# mattduino_mega.net
KiCad netlist of a schematic drawn in EAGLE
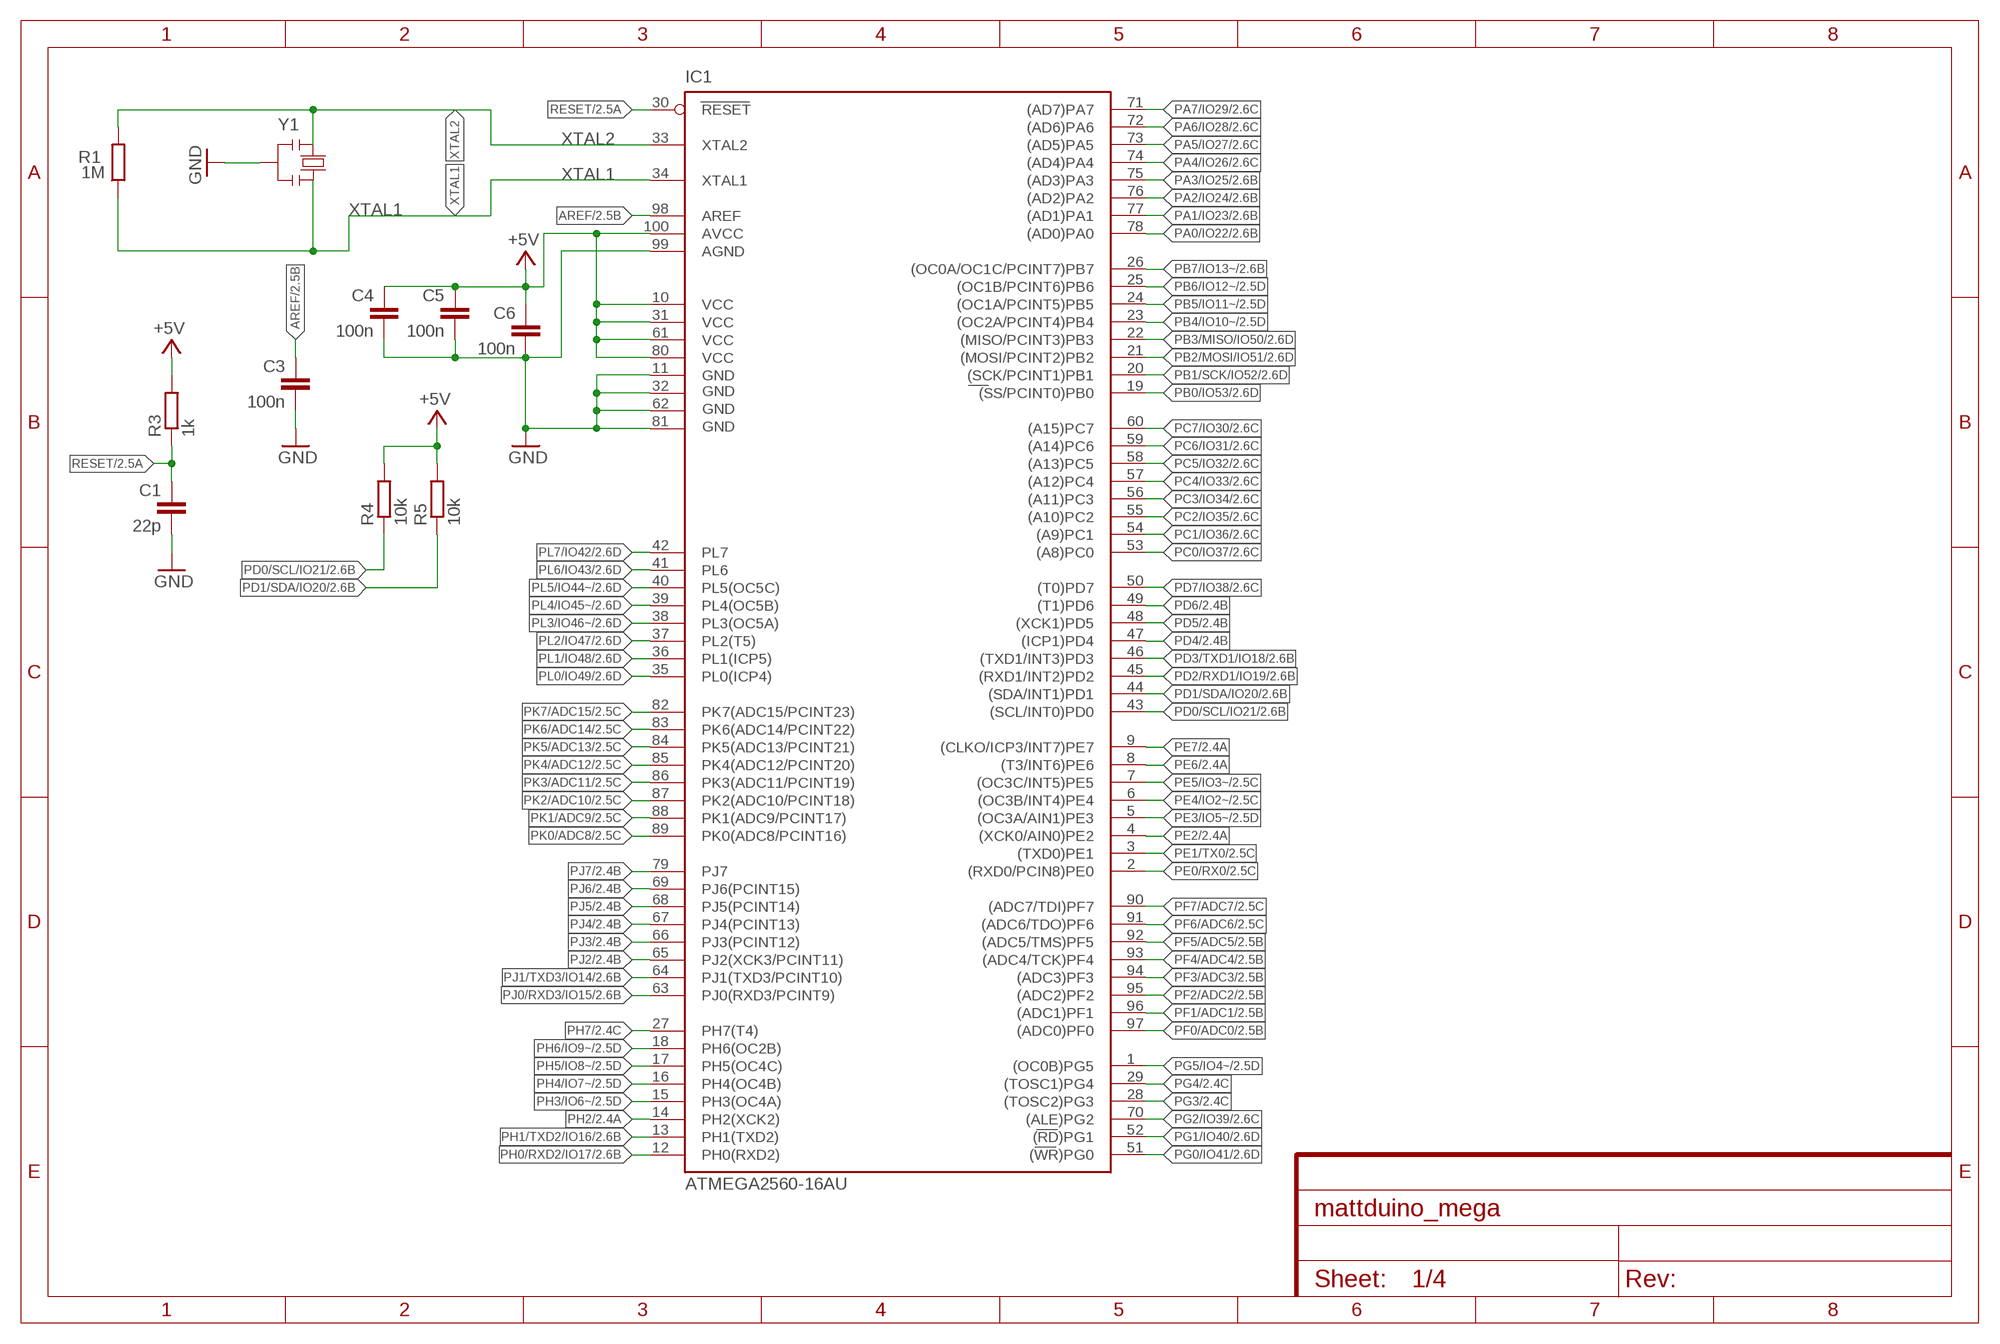
[diagram p0: schematic, sheet 1]
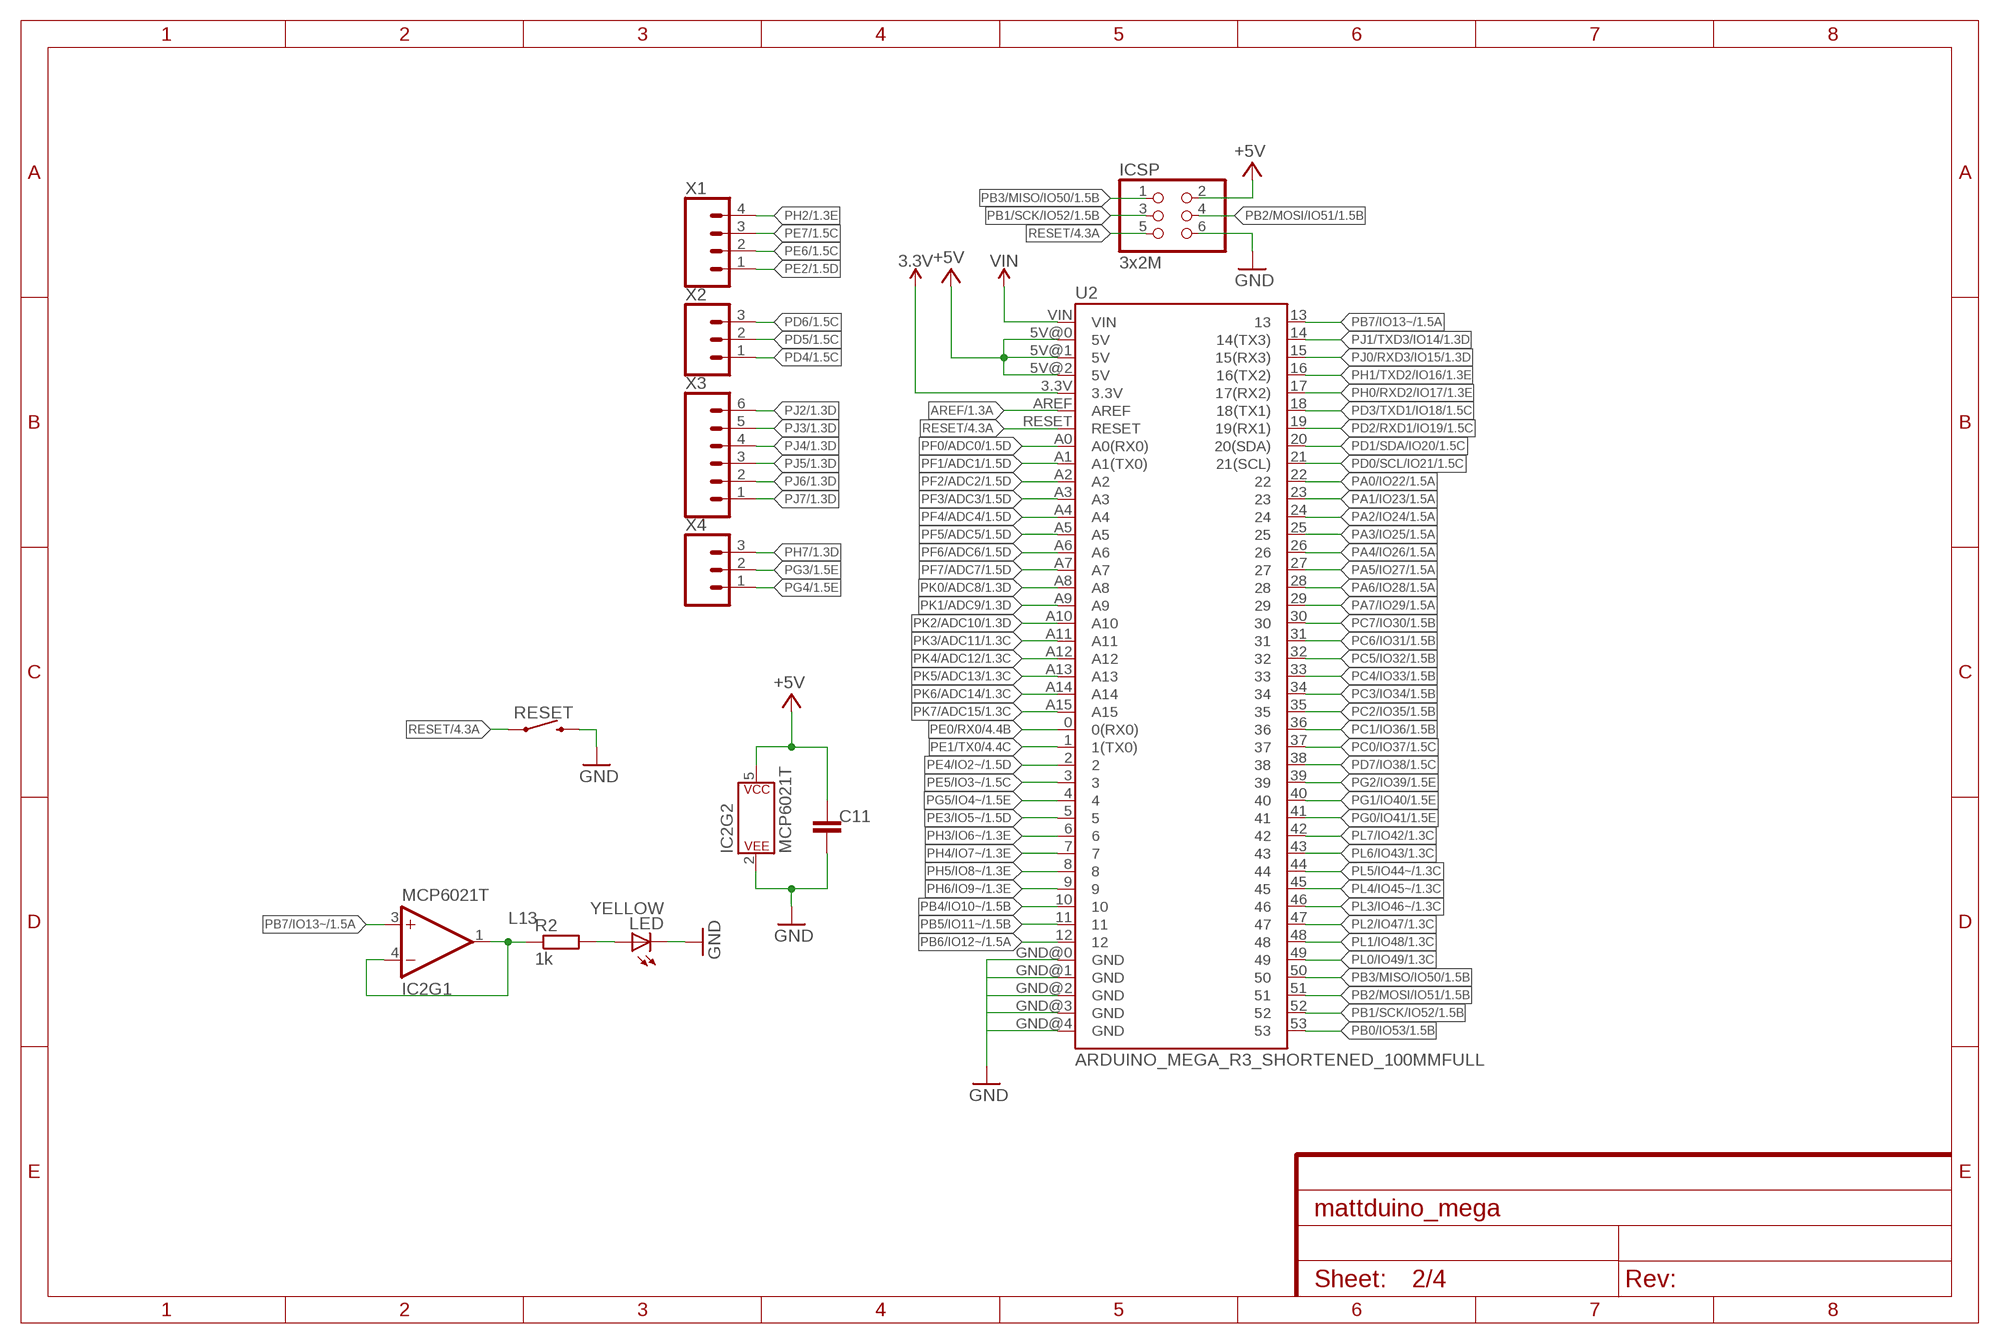
[diagram p1: schematic, sheet 2]
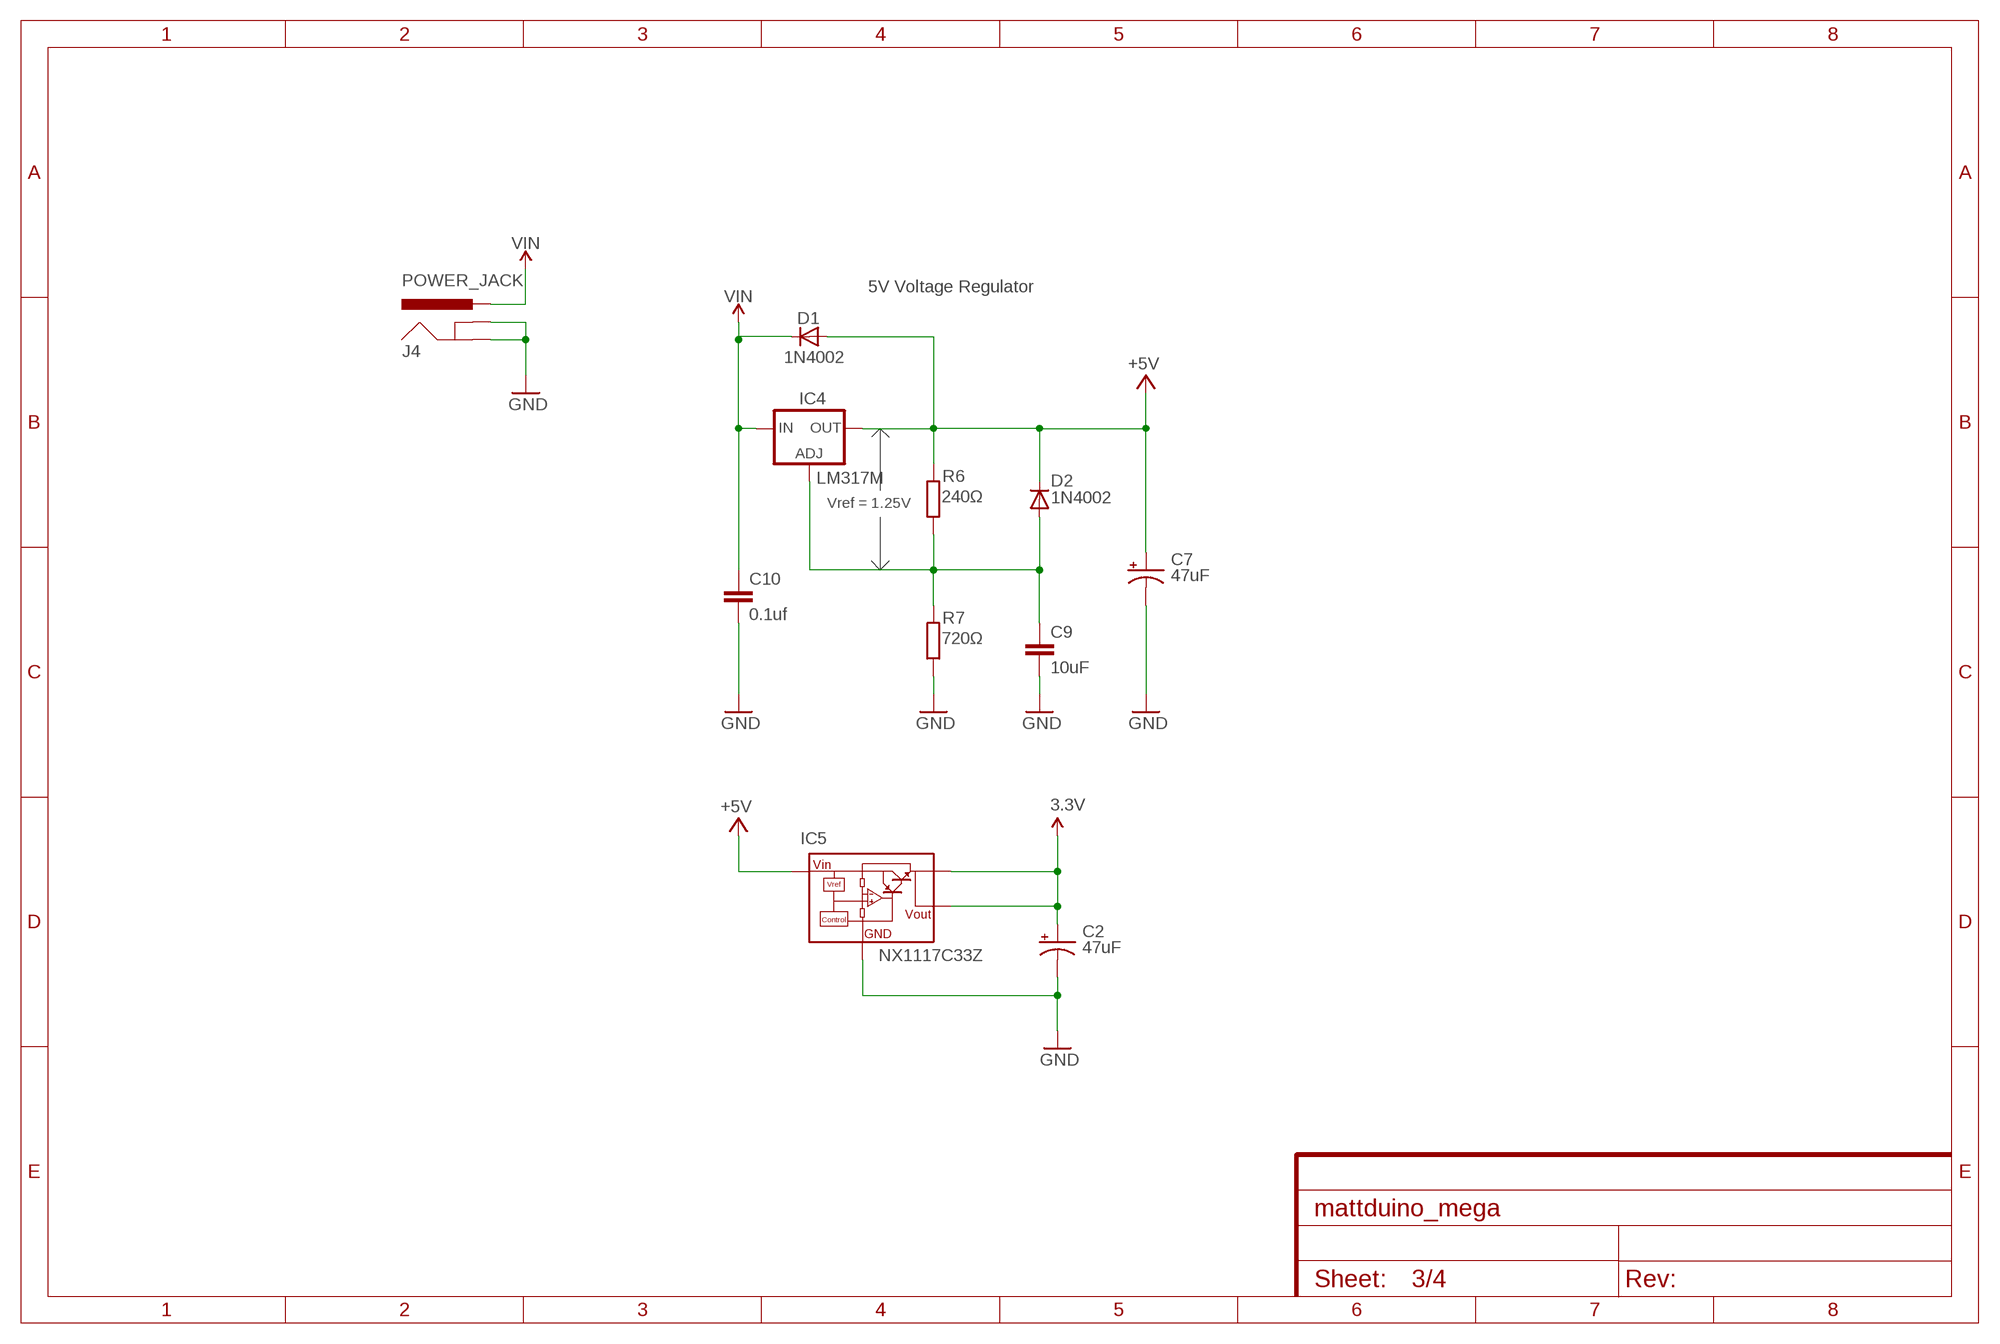
[diagram p2: schematic, sheet 3]
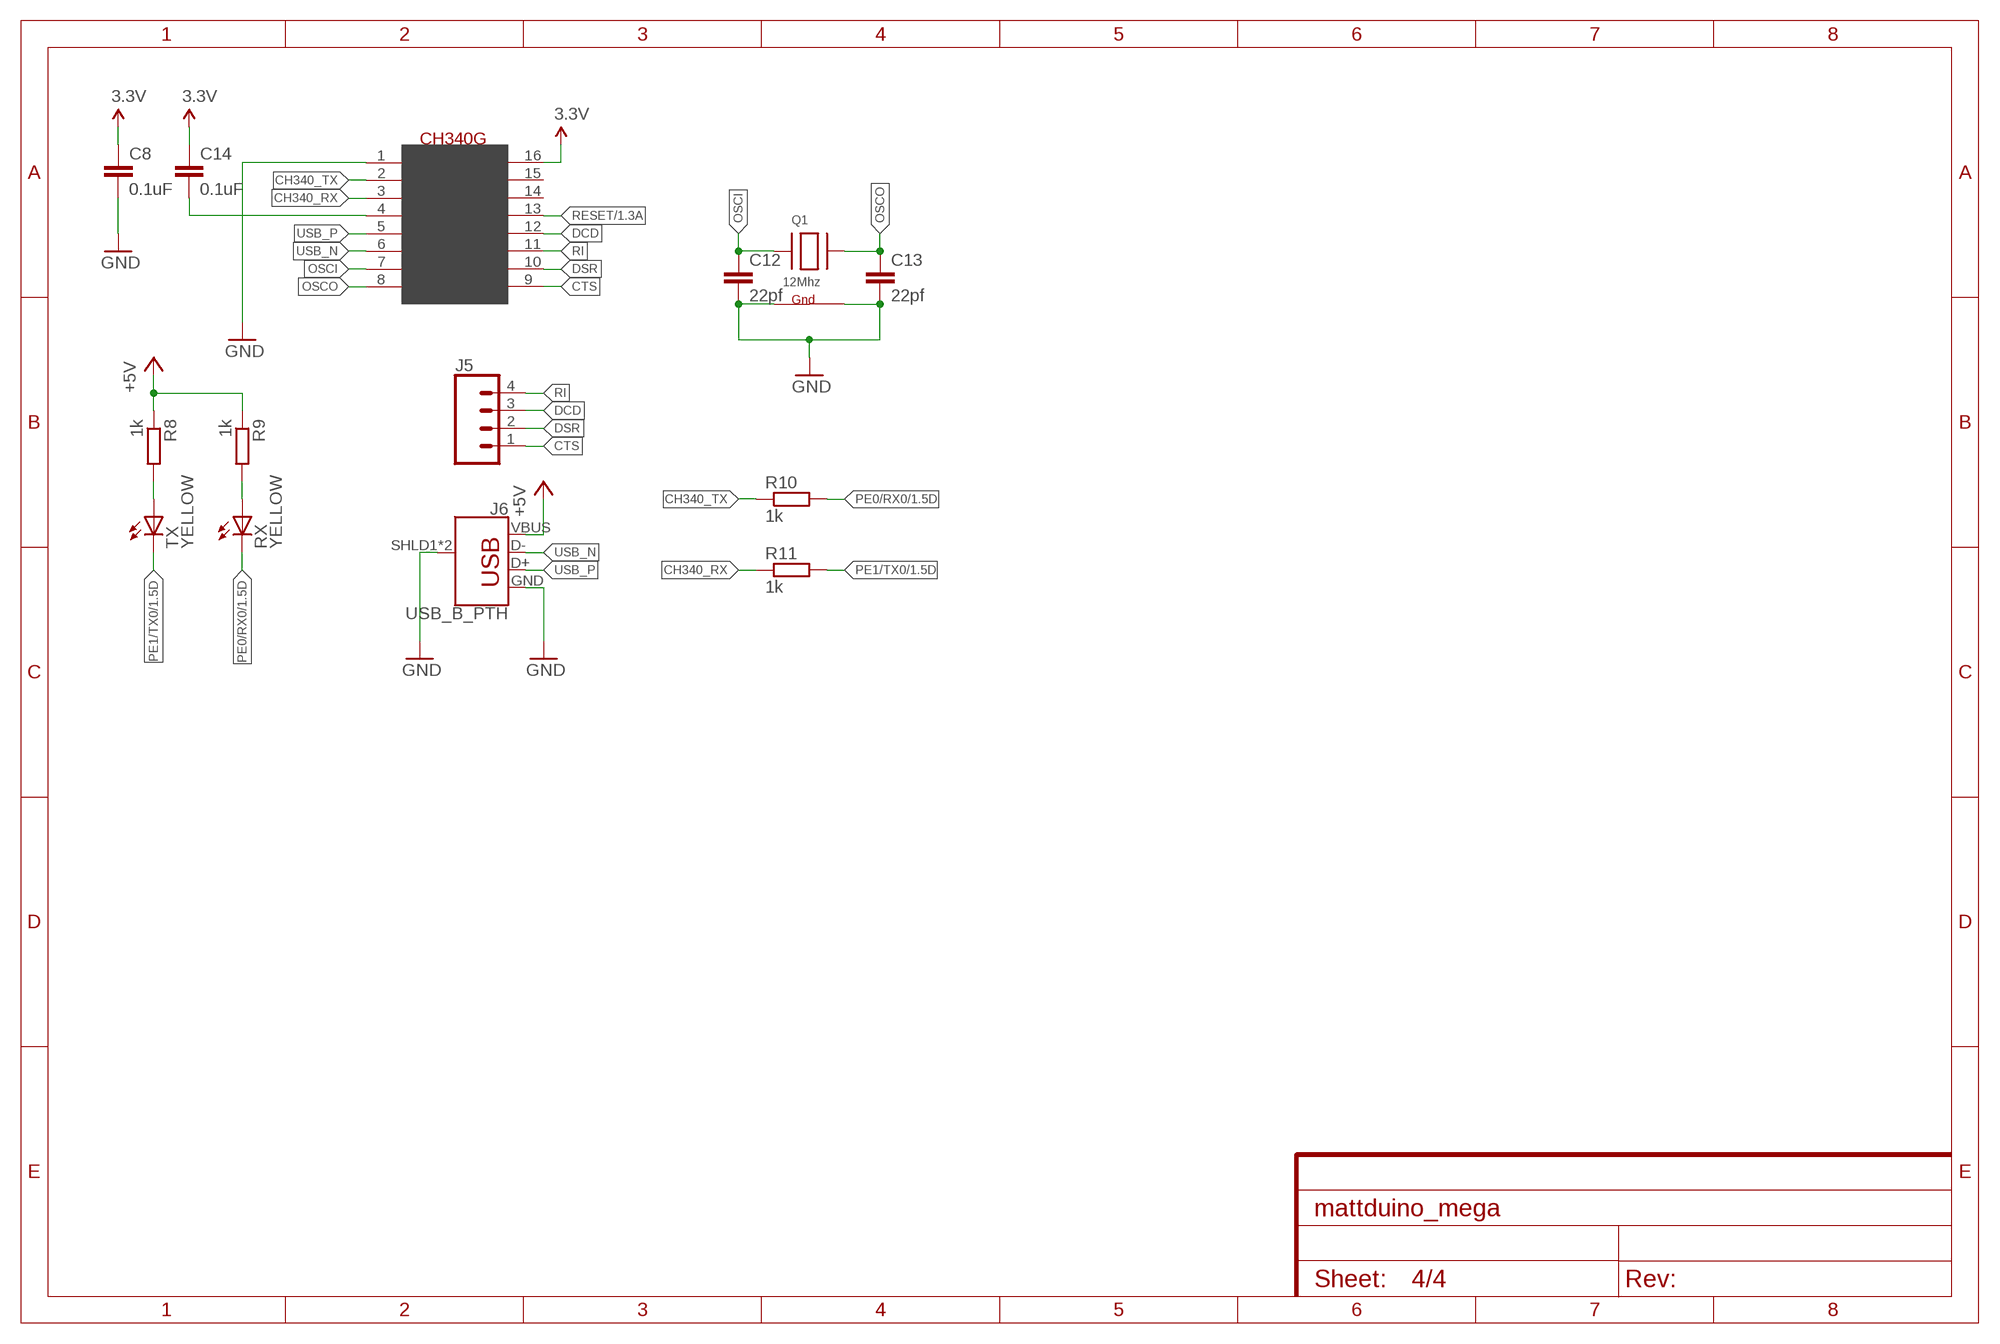
[diagram p3: schematic, sheet 4]

(export (version "E")
  (design (tool "Eeschema 10.0.6"))
  (components
    (comp (ref "C11")
      (value "100n")
      (footprint "eagle-import:C1206")
      (libsource (lib "eagle-import") (part "rcl_334_C-EUC1206"))
    )
    (comp (ref "IC2")
      (value "MCP6021T")
      (footprint "eagle-import:SOT23-5")
      (libsource (lib "eagle-import") (part "MCP6021T-E/OT"))
    )
    (comp (ref "ICSP")
      (value "3x2M")
      (footprint "eagle-import:2X03")
      (libsource (lib "eagle-import") (part "PINHD-2X3"))
    )
    (comp (ref "LED")
      (value "YELLOW")
      (footprint "eagle-import:CHIP-LED0805")
      (libsource (lib "eagle-import") (part "LEDCHIP-LED0805"))
    )
    (comp (ref "R2")
      (value "1k")
      (footprint "eagle-import:R1206")
      (libsource (lib "eagle-import") (part "R-EU_R1206"))
    )
    (comp (ref "RESET")
      (value "MOMENTARY-SWITCH-SPST-PTH-6.0MM")
      (footprint "eagle-import:TACTILE_SWITCH_PTH_6.0MM")
      (libsource (lib "eagle-import") (part "MOMENTARY-SWITCH-SPST-PTH-6.0MM"))
    )
    (comp (ref "U2")
      (value "ARDUINO_MEGA_R3_SHORTENED_100MMFULL")
      (footprint "eagle-import:ARDUINO_MEGA_SHORTENED_100MM")
      (libsource (lib "eagle-import") (part "ARDUINO_MEGA_R3_SHORTENED_100MMFULL"))
    )
    (comp (ref "X1")
      (value "CONN_04")
      (footprint "eagle-import:1X04")
      (libsource (lib "eagle-import") (part "CONN_04"))
    )
    (comp (ref "X2")
      (value "CONN_03")
      (footprint "eagle-import:1X03")
      (libsource (lib "eagle-import") (part "CONN_03"))
    )
    (comp (ref "X3")
      (value "CONN_06SILK_FEMALE_PTH")
      (footprint "eagle-import:1X06")
      (libsource (lib "eagle-import") (part "CONN_06SILK_FEMALE_PTH"))
    )
    (comp (ref "X4")
      (value "CONN_03")
      (footprint "eagle-import:1X03")
      (libsource (lib "eagle-import") (part "CONN_03"))
    )
    (comp (ref "C8")
      (value "0.1uF")
      (footprint "eagle-import:C1206")
      (libsource (lib "eagle-import") (part "rcl_334_C-EUC1206"))
    )
    (comp (ref "C12")
      (value "22pf")
      (footprint "eagle-import:C1206")
      (libsource (lib "eagle-import") (part "C-EUC1206"))
    )
    (comp (ref "C13")
      (value "22pf")
      (footprint "eagle-import:C1206")
      (libsource (lib "eagle-import") (part "C-EUC1206"))
    )
    (comp (ref "C14")
      (value "0.1uF")
      (footprint "eagle-import:C1206")
      (libsource (lib "eagle-import") (part "rcl_334_C-EUC1206"))
    )
    (comp (ref "IC3")
      (value "CH340G")
      (footprint "eagle-import:SOIC16")
      (libsource (lib "eagle-import") (part "CH340G"))
    )
    (comp (ref "J5")
      (value "CONN_04")
      (footprint "eagle-import:1X04")
      (libsource (lib "eagle-import") (part "CONN_04"))
    )
    (comp (ref "J6")
      (value "USB_B_PTH")
      (footprint "eagle-import:USB-B-PTH")
      (libsource (lib "eagle-import") (part "USB_B_PTH"))
    )
    (comp (ref "Q1")
      (value "12Mhz")
      (footprint "eagle-import:NX3225")
      (libsource (lib "eagle-import") (part "XTAL-4-3225"))
    )
    (comp (ref "R8")
      (value "1k")
      (footprint "eagle-import:R1206")
      (libsource (lib "eagle-import") (part "R-EU_R1206"))
    )
    (comp (ref "R9")
      (value "1k")
      (footprint "eagle-import:R1206")
      (libsource (lib "eagle-import") (part "R-EU_R1206"))
    )
    (comp (ref "R10")
      (value "1k")
      (footprint "eagle-import:R1206")
      (libsource (lib "eagle-import") (part "R-EU_R1206"))
    )
    (comp (ref "R11")
      (value "1k")
      (footprint "eagle-import:R1206")
      (libsource (lib "eagle-import") (part "R-EU_R1206"))
    )
    (comp (ref "RX")
      (value "YELLOW")
      (footprint "eagle-import:CHIP-LED0805")
      (libsource (lib "eagle-import") (part "LEDCHIP-LED0805"))
    )
    (comp (ref "TX")
      (value "YELLOW")
      (footprint "eagle-import:CHIP-LED0805")
      (libsource (lib "eagle-import") (part "LEDCHIP-LED0805"))
    )
    (comp (ref "C1")
      (value "22p")
      (footprint "eagle-import:C1206")
      (libsource (lib "eagle-import") (part "rcl_334_C-EUC1206"))
    )
    (comp (ref "C3")
      (value "100n")
      (footprint "eagle-import:C1206")
      (libsource (lib "eagle-import") (part "rcl_334_C-EUC1206"))
    )
    (comp (ref "C4")
      (value "100n")
      (footprint "eagle-import:C1206")
      (libsource (lib "eagle-import") (part "rcl_334_C-EUC1206"))
    )
    (comp (ref "C5")
      (value "100n")
      (footprint "eagle-import:C1206")
      (libsource (lib "eagle-import") (part "rcl_334_C-EUC1206"))
    )
    (comp (ref "C6")
      (value "100n")
      (footprint "eagle-import:C1206")
      (libsource (lib "eagle-import") (part "rcl_334_C-EUC1206"))
    )
    (comp (ref "IC1")
      (value "ATMEGA2560-16AU")
      (footprint "eagle-import:TQFP100")
      (libsource (lib "eagle-import") (part "ATMEGA2560AU2560-16"))
    )
    (comp (ref "R1")
      (value "1M")
      (footprint "eagle-import:R1206")
      (libsource (lib "eagle-import") (part "R-EU_R1206"))
    )
    (comp (ref "R3")
      (value "1k")
      (footprint "eagle-import:R1206")
      (libsource (lib "eagle-import") (part "R-EU_R1206"))
    )
    (comp (ref "R4")
      (value "10k")
      (footprint "eagle-import:R1206")
      (libsource (lib "eagle-import") (part "R-EU_R1206"))
    )
    (comp (ref "R5")
      (value "10k")
      (footprint "eagle-import:R1206")
      (libsource (lib "eagle-import") (part "R-EU_R1206"))
    )
    (comp (ref "Y1")
      (value "CSTCE16M0V53-R0 16MHZ")
      (footprint "eagle-import:RESONATOR")
      (libsource (lib "eagle-import") (part "RESONATORMU"))
    )
    (comp (ref "C2")
      (value "47uF")
      (footprint "eagle-import:PANASONIC_D")
      (libsource (lib "eagle-import") (part "47UF-POLAR-PANASONIC_D-35V-20%"))
    )
    (comp (ref "C7")
      (value "47uF")
      (footprint "eagle-import:PANASONIC_D")
      (libsource (lib "eagle-import") (part "47UF-POLAR-PANASONIC_D-35V-20%"))
    )
    (comp (ref "C9")
      (value "10uF")
      (footprint "eagle-import:C1206")
      (libsource (lib "eagle-import") (part "rcl_334_C-EUC1206"))
    )
    (comp (ref "C10")
      (value "0.1uf")
      (footprint "eagle-import:C1206")
      (libsource (lib "eagle-import") (part "rcl_334_C-EUC1206"))
    )
    (comp (ref "D1")
      (value "1N4002")
      (footprint "eagle-import:SOD-123")
      (libsource (lib "eagle-import") (part "DIODESOD-123"))
    )
    (comp (ref "D2")
      (value "1N4002")
      (footprint "eagle-import:SOD-123")
      (libsource (lib "eagle-import") (part "DIODESOD-123"))
    )
    (comp (ref "IC4")
      (value "LM317MBSTT3")
      (footprint "eagle-import:SOT223")
      (fields (field (name "PARTNUMBER") "LM317M"))
      (libsource (lib "eagle-import") (part "LM317?MBSTT3"))
    )
    (comp (ref "IC5")
      (value "NX1117C33Z")
      (footprint "eagle-import:SOT223")
      (fields (field (name "TOLERANCE") "1.25%") (field (name "VOLTAGE") "5.0V"))
      (libsource (lib "eagle-import") (part "NX1117CZ33"))
    )
    (comp (ref "J4")
      (value "POWER_JACK")
      (footprint "eagle-import:POWER_JACK_PTH")
      (libsource (lib "eagle-import") (part "POWER_JACK"))
    )
    (comp (ref "R6")
      (value "240Ω")
      (footprint "eagle-import:R1206")
      (libsource (lib "eagle-import") (part "R-EU_R1206"))
    )
    (comp (ref "R7")
      (value "720Ω")
      (footprint "eagle-import:R1206")
      (libsource (lib "eagle-import") (part "R-EU_R1206"))
    )
  )
  (nets
    (net (code "1") (name "+5V") (class "Default")
      (node (ref "C11") (pin "2") (pinfunction "2_2") (pintype "passive"))
      (node (ref "C4") (pin "1") (pinfunction "1_1") (pintype "passive"))
      (node (ref "C5") (pin "1") (pinfunction "1_1") (pintype "passive"))
      (node (ref "C6") (pin "1") (pinfunction "1_1") (pintype "passive"))
      (node (ref "C7") (pin "+") (pinfunction "+_+") (pintype "passive"))
      (node (ref "D1") (pin "A") (pinfunction "A_A") (pintype "passive"))
      (node (ref "D2") (pin "C") (pinfunction "C_C") (pintype "passive"))
      (node (ref "IC1") (pin "10") (pinfunction "VCC_10") (pintype "power_in"))
      (node (ref "IC1") (pin "100") (pinfunction "AVCC_100") (pintype "power_in"))
      (node (ref "IC1") (pin "31") (pinfunction "VCC1_31") (pintype "power_in"))
      (node (ref "IC1") (pin "61") (pinfunction "VCC2_61") (pintype "power_in"))
      (node (ref "IC1") (pin "80") (pinfunction "VCC3_80") (pintype "power_in"))
      (node (ref "IC2") (pin "5") (pinfunction "P$V+_5") (pintype "bidirectional"))
      (node (ref "IC4") (pin "4") (pinfunction "OUT_4") (pintype "passive"))
      (node (ref "IC5") (pin "3") (pinfunction "VIN_3") (pintype "input"))
      (node (ref "ICSP") (pin "2") (pinfunction "2_2") (pintype "passive"))
      (node (ref "J6") (pin "VBUS") (pinfunction "VBUS_VBUS") (pintype "power_in"))
      (node (ref "R3") (pin "2") (pinfunction "2_2") (pintype "passive"))
      (node (ref "R4") (pin "2") (pinfunction "2_2") (pintype "passive"))
      (node (ref "R5") (pin "2") (pinfunction "2_2") (pintype "passive"))
      (node (ref "R6") (pin "2") (pinfunction "2_2") (pintype "passive"))
      (node (ref "R8") (pin "1") (pinfunction "1_1") (pintype "passive"))
      (node (ref "R9") (pin "1") (pinfunction "1_1") (pintype "passive"))
      (node (ref "U2") (pin "5V@0") (pinfunction "5V_5V@0") (pintype "bidirectional"))
      (node (ref "U2") (pin "5V@1") (pinfunction "5V_5V@1") (pintype "bidirectional"))
      (node (ref "U2") (pin "5V@2") (pinfunction "5V_5V@2") (pintype "bidirectional"))
    )
    (net (code "2") (name "3.3V") (class "Default")
      (node (ref "C14") (pin "1") (pinfunction "1_1") (pintype "passive"))
      (node (ref "C2") (pin "+") (pinfunction "+_+") (pintype "passive"))
      (node (ref "C8") (pin "1") (pinfunction "1_1") (pintype "passive"))
      (node (ref "IC3") (pin "16") (pinfunction "VCC_16") (pintype "bidirectional"))
      (node (ref "IC5") (pin "2") (pinfunction "VOUT1_2") (pintype "output"))
      (node (ref "IC5") (pin "4") (pinfunction "VOUT_4") (pintype "output"))
      (node (ref "U2") (pin "3.3V") (pinfunction "3.3V_3.3V") (pintype "bidirectional"))
    )
    (net (code "3") (name "AREF") (class "Default")
      (node (ref "C3") (pin "1") (pinfunction "1_1") (pintype "passive"))
      (node (ref "IC1") (pin "98") (pinfunction "AREF_98") (pintype "bidirectional"))
      (node (ref "U2") (pin "AREF") (pinfunction "AREF_AREF") (pintype "bidirectional"))
    )
    (net (code "4") (name "CH340_RX") (class "Default")
      (node (ref "IC3") (pin "3") (pinfunction "RX_3") (pintype "bidirectional"))
      (node (ref "R11") (pin "1") (pinfunction "1_1") (pintype "passive"))
    )
    (net (code "5") (name "CH340_TX") (class "Default")
      (node (ref "IC3") (pin "2") (pinfunction "TX_2") (pintype "bidirectional"))
      (node (ref "R10") (pin "1") (pinfunction "1_1") (pintype "passive"))
    )
    (net (code "6") (name "CTS") (class "Default")
      (node (ref "IC3") (pin "9") (pinfunction "CTS_9") (pintype "bidirectional"))
      (node (ref "J5") (pin "1") (pinfunction "1_1") (pintype "passive"))
    )
    (net (code "7") (name "DCD") (class "Default")
      (node (ref "IC3") (pin "12") (pinfunction "DCD_12") (pintype "bidirectional"))
      (node (ref "J5") (pin "3") (pinfunction "3_3") (pintype "passive"))
    )
    (net (code "8") (name "DSR") (class "Default")
      (node (ref "IC3") (pin "10") (pinfunction "DSR_10") (pintype "bidirectional"))
      (node (ref "J5") (pin "2") (pinfunction "2_2") (pintype "passive"))
    )
    (net (code "9") (name "GND") (class "Default")
      (node (ref "C1") (pin "2") (pinfunction "2_2") (pintype "passive"))
      (node (ref "C10") (pin "2") (pinfunction "2_2") (pintype "passive"))
      (node (ref "C11") (pin "1") (pinfunction "1_1") (pintype "passive"))
      (node (ref "C12") (pin "2") (pinfunction "2_2") (pintype "passive"))
      (node (ref "C13") (pin "2") (pinfunction "2_2") (pintype "passive"))
      (node (ref "C2") (pin "-") (pinfunction "-_-") (pintype "passive"))
      (node (ref "C3") (pin "2") (pinfunction "2_2") (pintype "passive"))
      (node (ref "C4") (pin "2") (pinfunction "2_2") (pintype "passive"))
      (node (ref "C5") (pin "2") (pinfunction "2_2") (pintype "passive"))
      (node (ref "C6") (pin "2") (pinfunction "2_2") (pintype "passive"))
      (node (ref "C7") (pin "-") (pinfunction "-_-") (pintype "passive"))
      (node (ref "C8") (pin "2") (pinfunction "2_2") (pintype "passive"))
      (node (ref "C9") (pin "2") (pinfunction "2_2") (pintype "passive"))
      (node (ref "IC1") (pin "11") (pinfunction "GND_11") (pintype "power_in"))
      (node (ref "IC1") (pin "32") (pinfunction "GND1_32") (pintype "power_in"))
      (node (ref "IC1") (pin "62") (pinfunction "GND2_62") (pintype "power_in"))
      (node (ref "IC1") (pin "81") (pinfunction "GND3_81") (pintype "power_in"))
      (node (ref "IC1") (pin "99") (pinfunction "AGND_99") (pintype "power_in"))
      (node (ref "IC2") (pin "2") (pinfunction "P$V-_2") (pintype "bidirectional"))
      (node (ref "IC3") (pin "1") (pinfunction "GND_1") (pintype "bidirectional"))
      (node (ref "IC5") (pin "1") (pinfunction "GND_1") (pintype "passive"))
      (node (ref "ICSP") (pin "6") (pinfunction "6_6") (pintype "passive"))
      (node (ref "J4") (pin "GND") (pinfunction "GND_GND") (pintype "bidirectional"))
      (node (ref "J4") (pin "GNDBREAK") (pinfunction "GNDBREAK_GNDBREAK") (pintype "bidirectional"))
      (node (ref "J6") (pin "GND") (pinfunction "GND_GND") (pintype "power_in"))
      (node (ref "J6") (pin "SHLD1") (pinfunction "SHIELD_SHLD1") (pintype "bidirectional"))
      (node (ref "J6") (pin "SHLD2") (pinfunction "SHIELD_SHLD2") (pintype "bidirectional"))
      (node (ref "LED") (pin "C") (pinfunction "C_C") (pintype "passive"))
      (node (ref "Q1") (pin "2") (pinfunction "G2_2") (pintype "power_in"))
      (node (ref "Q1") (pin "4") (pinfunction "G1_4") (pintype "power_in"))
      (node (ref "R7") (pin "1") (pinfunction "1_1") (pintype "passive"))
      (node (ref "RESET") (pin "3") (pinfunction "2_3") (pintype "passive"))
      (node (ref "U2") (pin "GND@0") (pinfunction "GND_GND@0") (pintype "bidirectional"))
      (node (ref "U2") (pin "GND@1") (pinfunction "GND_GND@1") (pintype "bidirectional"))
      (node (ref "U2") (pin "GND@2") (pinfunction "GND_GND@2") (pintype "bidirectional"))
      (node (ref "U2") (pin "GND@3") (pinfunction "GND_GND@3") (pintype "bidirectional"))
      (node (ref "U2") (pin "GND@4") (pinfunction "GND_GND@4") (pintype "bidirectional"))
      (node (ref "Y1") (pin "2") (pinfunction "2_2") (pintype "passive"))
    )
    (net (code "10") (name "L13") (class "Default")
      (node (ref "IC2") (pin "1") (pinfunction "OUT_1") (pintype "output"))
      (node (ref "IC2") (pin "4") (pinfunction "-IN_4") (pintype "input"))
      (node (ref "R2") (pin "1") (pinfunction "1_1") (pintype "passive"))
    )
    (net (code "11") (name "Net-(IC3-V3)") (class "Default")
      (node (ref "C14") (pin "2") (pinfunction "2_2") (pintype "passive"))
      (node (ref "IC3") (pin "4") (pinfunction "V3_4") (pintype "bidirectional"))
    )
    (net (code "12") (name "Net-(IC4-ADJ)") (class "Default")
      (node (ref "C9") (pin "1") (pinfunction "1_1") (pintype "passive"))
      (node (ref "D2") (pin "A") (pinfunction "A_A") (pintype "passive"))
      (node (ref "IC4") (pin "1") (pinfunction "ADJ_1") (pintype "input"))
      (node (ref "R6") (pin "1") (pinfunction "1_1") (pintype "passive"))
      (node (ref "R7") (pin "2") (pinfunction "2_2") (pintype "passive"))
    )
    (net (code "13") (name "Net-(LED-PadA)") (class "Default")
      (node (ref "LED") (pin "A") (pinfunction "A_A") (pintype "passive"))
      (node (ref "R2") (pin "2") (pinfunction "2_2") (pintype "passive"))
    )
    (net (code "14") (name "Net-(R8-Pad2)") (class "Default")
      (node (ref "R8") (pin "2") (pinfunction "2_2") (pintype "passive"))
      (node (ref "TX") (pin "A") (pinfunction "A_A") (pintype "passive"))
    )
    (net (code "15") (name "Net-(R9-Pad2)") (class "Default")
      (node (ref "R9") (pin "2") (pinfunction "2_2") (pintype "passive"))
      (node (ref "RX") (pin "A") (pinfunction "A_A") (pintype "passive"))
    )
    (net (code "16") (name "OSCI") (class "Default")
      (node (ref "C12") (pin "1") (pinfunction "1_1") (pintype "passive"))
      (node (ref "IC3") (pin "7") (pinfunction "XI_7") (pintype "bidirectional"))
      (node (ref "Q1") (pin "1") (pinfunction "X1_1") (pintype "bidirectional"))
    )
    (net (code "17") (name "OSCO") (class "Default")
      (node (ref "C13") (pin "1") (pinfunction "1_1") (pintype "passive"))
      (node (ref "IC3") (pin "8") (pinfunction "XO_8") (pintype "bidirectional"))
      (node (ref "Q1") (pin "3") (pinfunction "X2_3") (pintype "bidirectional"))
    )
    (net (code "18") (name "PA0{slash}IO22") (class "Default")
      (node (ref "IC1") (pin "78") (pinfunction "(AD0)PA0_78") (pintype "bidirectional"))
      (node (ref "U2") (pin "22") (pinfunction "22_22") (pintype "bidirectional"))
    )
    (net (code "19") (name "PA1{slash}IO23") (class "Default")
      (node (ref "IC1") (pin "77") (pinfunction "(AD1)PA1_77") (pintype "bidirectional"))
      (node (ref "U2") (pin "23") (pinfunction "23_23") (pintype "bidirectional"))
    )
    (net (code "20") (name "PA2{slash}IO24") (class "Default")
      (node (ref "IC1") (pin "76") (pinfunction "(AD2)PA2_76") (pintype "bidirectional"))
      (node (ref "U2") (pin "24") (pinfunction "24_24") (pintype "bidirectional"))
    )
    (net (code "21") (name "PA3{slash}IO25") (class "Default")
      (node (ref "IC1") (pin "75") (pinfunction "(AD3)PA3_75") (pintype "bidirectional"))
      (node (ref "U2") (pin "25") (pinfunction "25_25") (pintype "bidirectional"))
    )
    (net (code "22") (name "PA4{slash}IO26") (class "Default")
      (node (ref "IC1") (pin "74") (pinfunction "(AD4)PA4_74") (pintype "bidirectional"))
      (node (ref "U2") (pin "26") (pinfunction "26_26") (pintype "bidirectional"))
    )
    (net (code "23") (name "PA5{slash}IO27") (class "Default")
      (node (ref "IC1") (pin "73") (pinfunction "(AD5)PA5_73") (pintype "bidirectional"))
      (node (ref "U2") (pin "27") (pinfunction "27_27") (pintype "bidirectional"))
    )
    (net (code "24") (name "PA6{slash}IO28") (class "Default")
      (node (ref "IC1") (pin "72") (pinfunction "(AD6)PA6_72") (pintype "bidirectional"))
      (node (ref "U2") (pin "28") (pinfunction "28_28") (pintype "bidirectional"))
    )
    (net (code "25") (name "PA7{slash}IO29") (class "Default")
      (node (ref "IC1") (pin "71") (pinfunction "(AD7)PA7_71") (pintype "bidirectional"))
      (node (ref "U2") (pin "29") (pinfunction "29_29") (pintype "bidirectional"))
    )
    (net (code "26") (name "PB0{slash}IO53") (class "Default")
      (node (ref "IC1") (pin "19") (pinfunction "(SS/PCINT0)PB0_19") (pintype "bidirectional"))
      (node (ref "U2") (pin "53") (pinfunction "53_53") (pintype "bidirectional"))
    )
    (net (code "27") (name "PB1{slash}SCK{slash}IO52") (class "Default")
      (node (ref "IC1") (pin "20") (pinfunction "(SCK/PCINT1)PB1_20") (pintype "bidirectional"))
      (node (ref "ICSP") (pin "3") (pinfunction "3_3") (pintype "passive"))
      (node (ref "U2") (pin "52") (pinfunction "52_52") (pintype "bidirectional"))
    )
    (net (code "28") (name "PB2{slash}MOSI{slash}IO51") (class "Default")
      (node (ref "IC1") (pin "21") (pinfunction "(MOSI/PCINT2)PB2_21") (pintype "bidirectional"))
      (node (ref "ICSP") (pin "4") (pinfunction "4_4") (pintype "passive"))
      (node (ref "U2") (pin "51") (pinfunction "51_51") (pintype "bidirectional"))
    )
    (net (code "29") (name "PB3{slash}MISO{slash}IO50") (class "Default")
      (node (ref "IC1") (pin "22") (pinfunction "(MISO/PCINT3)PB3_22") (pintype "bidirectional"))
      (node (ref "ICSP") (pin "1") (pinfunction "1_1") (pintype "passive"))
      (node (ref "U2") (pin "50") (pinfunction "50_50") (pintype "bidirectional"))
    )
    (net (code "30") (name "PB4{slash}IO10~{}") (class "Default")
      (node (ref "IC1") (pin "23") (pinfunction "(OC2A/PCINT4)PB4_23") (pintype "bidirectional"))
      (node (ref "U2") (pin "10") (pinfunction "10_10") (pintype "bidirectional"))
    )
    (net (code "31") (name "PB5{slash}IO11~{}") (class "Default")
      (node (ref "IC1") (pin "24") (pinfunction "(OC1A/PCINT5)PB5_24") (pintype "bidirectional"))
      (node (ref "U2") (pin "11") (pinfunction "11_11") (pintype "bidirectional"))
    )
    (net (code "32") (name "PB6{slash}IO12~{}") (class "Default")
      (node (ref "IC1") (pin "25") (pinfunction "(OC1B/PCINT6)PB6_25") (pintype "bidirectional"))
      (node (ref "U2") (pin "12") (pinfunction "12_12") (pintype "bidirectional"))
    )
    (net (code "33") (name "PB7{slash}IO13~{}") (class "Default")
      (node (ref "IC1") (pin "26") (pinfunction "(OC0A/OC1C/PCINT7)PB7_26") (pintype "bidirectional"))
      (node (ref "IC2") (pin "3") (pinfunction "+IN_3") (pintype "input"))
      (node (ref "U2") (pin "13") (pinfunction "13_13") (pintype "bidirectional"))
    )
    (net (code "34") (name "PC0{slash}IO37") (class "Default")
      (node (ref "IC1") (pin "53") (pinfunction "(A8)PC0_53") (pintype "bidirectional"))
      (node (ref "U2") (pin "37") (pinfunction "37_37") (pintype "bidirectional"))
    )
    (net (code "35") (name "PC1{slash}IO36") (class "Default")
      (node (ref "IC1") (pin "54") (pinfunction "(A9)PC1_54") (pintype "bidirectional"))
      (node (ref "U2") (pin "36") (pinfunction "36_36") (pintype "bidirectional"))
    )
    (net (code "36") (name "PC2{slash}IO35") (class "Default")
      (node (ref "IC1") (pin "55") (pinfunction "(A10)PC2_55") (pintype "bidirectional"))
      (node (ref "U2") (pin "35") (pinfunction "35_35") (pintype "bidirectional"))
    )
    (net (code "37") (name "PC3{slash}IO34") (class "Default")
      (node (ref "IC1") (pin "56") (pinfunction "(A11)PC3_56") (pintype "bidirectional"))
      (node (ref "U2") (pin "34") (pinfunction "34_34") (pintype "bidirectional"))
    )
    (net (code "38") (name "PC4{slash}IO33") (class "Default")
      (node (ref "IC1") (pin "57") (pinfunction "(A12)PC4_57") (pintype "bidirectional"))
      (node (ref "U2") (pin "33") (pinfunction "33_33") (pintype "bidirectional"))
    )
    (net (code "39") (name "PC5{slash}IO32") (class "Default")
      (node (ref "IC1") (pin "58") (pinfunction "(A13)PC5_58") (pintype "bidirectional"))
      (node (ref "U2") (pin "32") (pinfunction "32_32") (pintype "bidirectional"))
    )
    (net (code "40") (name "PC6{slash}IO31") (class "Default")
      (node (ref "IC1") (pin "59") (pinfunction "(A14)PC6_59") (pintype "bidirectional"))
      (node (ref "U2") (pin "31") (pinfunction "31_31") (pintype "bidirectional"))
    )
    (net (code "41") (name "PC7{slash}IO30") (class "Default")
      (node (ref "IC1") (pin "60") (pinfunction "(A15)PC7_60") (pintype "bidirectional"))
      (node (ref "U2") (pin "30") (pinfunction "30_30") (pintype "bidirectional"))
    )
    (net (code "42") (name "PD0{slash}SCL{slash}IO21") (class "Default")
      (node (ref "IC1") (pin "43") (pinfunction "(SCL/INT0)PD0_43") (pintype "bidirectional"))
      (node (ref "R4") (pin "1") (pinfunction "1_1") (pintype "passive"))
      (node (ref "U2") (pin "21") (pinfunction "21(SCL)_21") (pintype "bidirectional"))
    )
    (net (code "43") (name "PD1{slash}SDA{slash}IO20") (class "Default")
      (node (ref "IC1") (pin "44") (pinfunction "(SDA/INT1)PD1_44") (pintype "bidirectional"))
      (node (ref "R5") (pin "1") (pinfunction "1_1") (pintype "passive"))
      (node (ref "U2") (pin "20") (pinfunction "20(SDA)_20") (pintype "bidirectional"))
    )
    (net (code "44") (name "PD2{slash}RXD1{slash}IO19") (class "Default")
      (node (ref "IC1") (pin "45") (pinfunction "(RXD1/INT2)PD2_45") (pintype "bidirectional"))
      (node (ref "U2") (pin "19") (pinfunction "19(RX1)_19") (pintype "bidirectional"))
    )
    (net (code "45") (name "PD3{slash}TXD1{slash}IO18") (class "Default")
      (node (ref "IC1") (pin "46") (pinfunction "(TXD1/INT3)PD3_46") (pintype "bidirectional"))
      (node (ref "U2") (pin "18") (pinfunction "18(TX1)_18") (pintype "bidirectional"))
    )
    (net (code "46") (name "PD4") (class "Default")
      (node (ref "IC1") (pin "47") (pinfunction "(ICP1)PD4_47") (pintype "bidirectional"))
      (node (ref "X2") (pin "1") (pinfunction "1_1") (pintype "passive"))
    )
    (net (code "47") (name "PD5") (class "Default")
      (node (ref "IC1") (pin "48") (pinfunction "(XCK1)PD5_48") (pintype "bidirectional"))
      (node (ref "X2") (pin "2") (pinfunction "2_2") (pintype "passive"))
    )
    (net (code "48") (name "PD6") (class "Default")
      (node (ref "IC1") (pin "49") (pinfunction "(T1)PD6_49") (pintype "bidirectional"))
      (node (ref "X2") (pin "3") (pinfunction "3_3") (pintype "passive"))
    )
    (net (code "49") (name "PD7{slash}IO38") (class "Default")
      (node (ref "IC1") (pin "50") (pinfunction "(T0)PD7_50") (pintype "bidirectional"))
      (node (ref "U2") (pin "38") (pinfunction "38_38") (pintype "bidirectional"))
    )
    (net (code "50") (name "PE0{slash}RX0") (class "Default")
      (node (ref "IC1") (pin "2") (pinfunction "(RXD0/PCIN8)PE0_2") (pintype "bidirectional"))
      (node (ref "R10") (pin "2") (pinfunction "2_2") (pintype "passive"))
      (node (ref "RX") (pin "C") (pinfunction "C_C") (pintype "passive"))
      (node (ref "U2") (pin "0") (pinfunction "0(RX0)_0") (pintype "bidirectional"))
    )
    (net (code "51") (name "PE1{slash}TX0") (class "Default")
      (node (ref "IC1") (pin "3") (pinfunction "(TXD0)PE1_3") (pintype "bidirectional"))
      (node (ref "R11") (pin "2") (pinfunction "2_2") (pintype "passive"))
      (node (ref "TX") (pin "C") (pinfunction "C_C") (pintype "passive"))
      (node (ref "U2") (pin "1") (pinfunction "1(TX0)_1") (pintype "bidirectional"))
    )
    (net (code "52") (name "PE2") (class "Default")
      (node (ref "IC1") (pin "4") (pinfunction "(XCK0/AIN0)PE2_4") (pintype "bidirectional"))
      (node (ref "X1") (pin "1") (pinfunction "1_1") (pintype "passive"))
    )
    (net (code "53") (name "PE3{slash}IO5~{}") (class "Default")
      (node (ref "IC1") (pin "5") (pinfunction "(OC3A/AIN1)PE3_5") (pintype "bidirectional"))
      (node (ref "U2") (pin "5") (pinfunction "5_5") (pintype "bidirectional"))
    )
    (net (code "54") (name "PE4{slash}IO2~{}") (class "Default")
      (node (ref "IC1") (pin "6") (pinfunction "(OC3B/INT4)PE4_6") (pintype "bidirectional"))
      (node (ref "U2") (pin "2") (pinfunction "2_2") (pintype "bidirectional"))
    )
    (net (code "55") (name "PE5{slash}IO3~{}") (class "Default")
      (node (ref "IC1") (pin "7") (pinfunction "(OC3C/INT5)PE5_7") (pintype "bidirectional"))
      (node (ref "U2") (pin "3") (pinfunction "3_3") (pintype "bidirectional"))
    )
    (net (code "56") (name "PE6") (class "Default")
      (node (ref "IC1") (pin "8") (pinfunction "(T3/INT6)PE6_8") (pintype "bidirectional"))
      (node (ref "X1") (pin "2") (pinfunction "2_2") (pintype "passive"))
    )
    (net (code "57") (name "PE7") (class "Default")
      (node (ref "IC1") (pin "9") (pinfunction "(CLKO/ICP3/INT7)PE7_9") (pintype "bidirectional"))
      (node (ref "X1") (pin "3") (pinfunction "3_3") (pintype "passive"))
    )
    (net (code "58") (name "PF0{slash}ADC0") (class "Default")
      (node (ref "IC1") (pin "97") (pinfunction "(ADC0)PF0_97") (pintype "bidirectional"))
      (node (ref "U2") (pin "A0") (pinfunction "A0(RX0)_A0") (pintype "bidirectional"))
    )
    (net (code "59") (name "PF1{slash}ADC1") (class "Default")
      (node (ref "IC1") (pin "96") (pinfunction "(ADC1)PF1_96") (pintype "bidirectional"))
      (node (ref "U2") (pin "A1") (pinfunction "A1(TX0)_A1") (pintype "bidirectional"))
    )
    (net (code "60") (name "PF2{slash}ADC2") (class "Default")
      (node (ref "IC1") (pin "95") (pinfunction "(ADC2)PF2_95") (pintype "bidirectional"))
      (node (ref "U2") (pin "A2") (pinfunction "A2_A2") (pintype "bidirectional"))
    )
    (net (code "61") (name "PF3{slash}ADC3") (class "Default")
      (node (ref "IC1") (pin "94") (pinfunction "(ADC3)PF3_94") (pintype "bidirectional"))
      (node (ref "U2") (pin "A3") (pinfunction "A3_A3") (pintype "bidirectional"))
    )
    (net (code "62") (name "PF4{slash}ADC4") (class "Default")
      (node (ref "IC1") (pin "93") (pinfunction "(ADC4/TCK)PF4_93") (pintype "bidirectional"))
      (node (ref "U2") (pin "A4") (pinfunction "A4_A4") (pintype "bidirectional"))
    )
    (net (code "63") (name "PF5{slash}ADC5") (class "Default")
      (node (ref "IC1") (pin "92") (pinfunction "(ADC5/TMS)PF5_92") (pintype "bidirectional"))
      (node (ref "U2") (pin "A5") (pinfunction "A5_A5") (pintype "bidirectional"))
    )
    (net (code "64") (name "PF6{slash}ADC6") (class "Default")
      (node (ref "IC1") (pin "91") (pinfunction "(ADC6/TDO)PF6_91") (pintype "bidirectional"))
      (node (ref "U2") (pin "A6") (pinfunction "A6_A6") (pintype "bidirectional"))
    )
    (net (code "65") (name "PF7{slash}ADC7") (class "Default")
      (node (ref "IC1") (pin "90") (pinfunction "(ADC7/TDI)PF7_90") (pintype "bidirectional"))
      (node (ref "U2") (pin "A7") (pinfunction "A7_A7") (pintype "bidirectional"))
    )
    (net (code "66") (name "PG0{slash}IO41") (class "Default")
      (node (ref "IC1") (pin "51") (pinfunction "(WR)PG0_51") (pintype "bidirectional"))
      (node (ref "U2") (pin "41") (pinfunction "41_41") (pintype "bidirectional"))
    )
    (net (code "67") (name "PG1{slash}IO40") (class "Default")
      (node (ref "IC1") (pin "52") (pinfunction "(RD)PG1_52") (pintype "bidirectional"))
      (node (ref "U2") (pin "40") (pinfunction "40_40") (pintype "bidirectional"))
    )
    (net (code "68") (name "PG2{slash}IO39") (class "Default")
      (node (ref "IC1") (pin "70") (pinfunction "(ALE)PG2_70") (pintype "bidirectional"))
      (node (ref "U2") (pin "39") (pinfunction "39_39") (pintype "bidirectional"))
    )
    (net (code "69") (name "PG3") (class "Default")
      (node (ref "IC1") (pin "28") (pinfunction "(TOSC2)PG3_28") (pintype "bidirectional"))
      (node (ref "X4") (pin "2") (pinfunction "2_2") (pintype "passive"))
    )
    (net (code "70") (name "PG4") (class "Default")
      (node (ref "IC1") (pin "29") (pinfunction "(TOSC1)PG4_29") (pintype "bidirectional"))
      (node (ref "X4") (pin "1") (pinfunction "1_1") (pintype "passive"))
    )
    (net (code "71") (name "PG5{slash}IO4~{}") (class "Default")
      (node (ref "IC1") (pin "1") (pinfunction "(OC0B)PG5_1") (pintype "bidirectional"))
      (node (ref "U2") (pin "4") (pinfunction "4_4") (pintype "bidirectional"))
    )
    (net (code "72") (name "PH0{slash}RXD2{slash}IO17") (class "Default")
      (node (ref "IC1") (pin "12") (pinfunction "PH0(RXD2)_12") (pintype "bidirectional"))
      (node (ref "U2") (pin "17") (pinfunction "17(RX2)_17") (pintype "bidirectional"))
    )
    (net (code "73") (name "PH1{slash}TXD2{slash}IO16") (class "Default")
      (node (ref "IC1") (pin "13") (pinfunction "PH1(TXD2)_13") (pintype "bidirectional"))
      (node (ref "U2") (pin "16") (pinfunction "16(TX2)_16") (pintype "bidirectional"))
    )
    (net (code "74") (name "PH2") (class "Default")
      (node (ref "IC1") (pin "14") (pinfunction "PH2(XCK2)_14") (pintype "bidirectional"))
      (node (ref "X1") (pin "4") (pinfunction "4_4") (pintype "passive"))
    )
    (net (code "75") (name "PH3{slash}IO6~{}") (class "Default")
      (node (ref "IC1") (pin "15") (pinfunction "PH3(OC4A)_15") (pintype "bidirectional"))
      (node (ref "U2") (pin "6") (pinfunction "6_6") (pintype "bidirectional"))
    )
    (net (code "76") (name "PH4{slash}IO7~{}") (class "Default")
      (node (ref "IC1") (pin "16") (pinfunction "PH4(OC4B)_16") (pintype "bidirectional"))
      (node (ref "U2") (pin "7") (pinfunction "7_7") (pintype "bidirectional"))
    )
    (net (code "77") (name "PH5{slash}IO8~{}") (class "Default")
      (node (ref "IC1") (pin "17") (pinfunction "PH5(OC4C)_17") (pintype "bidirectional"))
      (node (ref "U2") (pin "8") (pinfunction "8_8") (pintype "bidirectional"))
    )
    (net (code "78") (name "PH6{slash}IO9~{}") (class "Default")
      (node (ref "IC1") (pin "18") (pinfunction "PH6(OC2B)_18") (pintype "bidirectional"))
      (node (ref "U2") (pin "9") (pinfunction "9_9") (pintype "bidirectional"))
    )
    (net (code "79") (name "PH7") (class "Default")
      (node (ref "IC1") (pin "27") (pinfunction "PH7(T4)_27") (pintype "bidirectional"))
      (node (ref "X4") (pin "3") (pinfunction "3_3") (pintype "passive"))
    )
    (net (code "80") (name "PJ0{slash}RXD3{slash}IO15") (class "Default")
      (node (ref "IC1") (pin "63") (pinfunction "PJ0(RXD3/PCINT9)_63") (pintype "bidirectional"))
      (node (ref "U2") (pin "15") (pinfunction "15(RX3)_15") (pintype "bidirectional"))
    )
    (net (code "81") (name "PJ1{slash}TXD3{slash}IO14") (class "Default")
      (node (ref "IC1") (pin "64") (pinfunction "PJ1(TXD3/PCINT10)_64") (pintype "bidirectional"))
      (node (ref "U2") (pin "14") (pinfunction "14(TX3)_14") (pintype "bidirectional"))
    )
    (net (code "82") (name "PJ2") (class "Default")
      (node (ref "IC1") (pin "65") (pinfunction "PJ2(XCK3/PCINT11)_65") (pintype "bidirectional"))
      (node (ref "X3") (pin "6") (pinfunction "6_6") (pintype "passive"))
    )
    (net (code "83") (name "PJ3") (class "Default")
      (node (ref "IC1") (pin "66") (pinfunction "PJ3(PCINT12)_66") (pintype "bidirectional"))
      (node (ref "X3") (pin "5") (pinfunction "5_5") (pintype "passive"))
    )
    (net (code "84") (name "PJ4") (class "Default")
      (node (ref "IC1") (pin "67") (pinfunction "PJ4(PCINT13)_67") (pintype "bidirectional"))
      (node (ref "X3") (pin "4") (pinfunction "4_4") (pintype "passive"))
    )
    (net (code "85") (name "PJ5") (class "Default")
      (node (ref "IC1") (pin "68") (pinfunction "PJ5(PCINT14)_68") (pintype "bidirectional"))
      (node (ref "X3") (pin "3") (pinfunction "3_3") (pintype "passive"))
    )
    (net (code "86") (name "PJ6") (class "Default")
      (node (ref "IC1") (pin "69") (pinfunction "PJ6(PCINT15)_69") (pintype "bidirectional"))
      (node (ref "X3") (pin "2") (pinfunction "2_2") (pintype "passive"))
    )
    (net (code "87") (name "PJ7") (class "Default")
      (node (ref "IC1") (pin "79") (pinfunction "PJ7_79") (pintype "bidirectional"))
      (node (ref "X3") (pin "1") (pinfunction "1_1") (pintype "passive"))
    )
    (net (code "88") (name "PK0{slash}ADC8") (class "Default")
      (node (ref "IC1") (pin "89") (pinfunction "PK0(ADC8/PCINT16)_89") (pintype "bidirectional"))
      (node (ref "U2") (pin "A8") (pinfunction "A8_A8") (pintype "bidirectional"))
    )
    (net (code "89") (name "PK1{slash}ADC9") (class "Default")
      (node (ref "IC1") (pin "88") (pinfunction "PK1(ADC9/PCINT17)_88") (pintype "bidirectional"))
      (node (ref "U2") (pin "A9") (pinfunction "A9_A9") (pintype "bidirectional"))
    )
    (net (code "90") (name "PK2{slash}ADC10") (class "Default")
      (node (ref "IC1") (pin "87") (pinfunction "PK2(ADC10/PCINT18)_87") (pintype "bidirectional"))
      (node (ref "U2") (pin "A10") (pinfunction "A10_A10") (pintype "bidirectional"))
    )
    (net (code "91") (name "PK3{slash}ADC11") (class "Default")
      (node (ref "IC1") (pin "86") (pinfunction "PK3(ADC11/PCINT19)_86") (pintype "bidirectional"))
      (node (ref "U2") (pin "A11") (pinfunction "A11_A11") (pintype "bidirectional"))
    )
    (net (code "92") (name "PK4{slash}ADC12") (class "Default")
      (node (ref "IC1") (pin "85") (pinfunction "PK4(ADC12/PCINT20)_85") (pintype "bidirectional"))
      (node (ref "U2") (pin "A12") (pinfunction "A12_A12") (pintype "bidirectional"))
    )
    (net (code "93") (name "PK5{slash}ADC13") (class "Default")
      (node (ref "IC1") (pin "84") (pinfunction "PK5(ADC13/PCINT21)_84") (pintype "bidirectional"))
      (node (ref "U2") (pin "A13") (pinfunction "A13_A13") (pintype "bidirectional"))
    )
    (net (code "94") (name "PK6{slash}ADC14") (class "Default")
      (node (ref "IC1") (pin "83") (pinfunction "PK6(ADC14/PCINT22)_83") (pintype "bidirectional"))
      (node (ref "U2") (pin "A14") (pinfunction "A14_A14") (pintype "bidirectional"))
    )
    (net (code "95") (name "PK7{slash}ADC15") (class "Default")
      (node (ref "IC1") (pin "82") (pinfunction "PK7(ADC15/PCINT23)_82") (pintype "bidirectional"))
      (node (ref "U2") (pin "A15") (pinfunction "A15_A15") (pintype "bidirectional"))
    )
    (net (code "96") (name "PL0{slash}IO49") (class "Default")
      (node (ref "IC1") (pin "35") (pinfunction "PL0(ICP4)_35") (pintype "bidirectional"))
      (node (ref "U2") (pin "49") (pinfunction "49_49") (pintype "bidirectional"))
    )
    (net (code "97") (name "PL1{slash}IO48") (class "Default")
      (node (ref "IC1") (pin "36") (pinfunction "PL1(ICP5)_36") (pintype "bidirectional"))
      (node (ref "U2") (pin "48") (pinfunction "48_48") (pintype "bidirectional"))
    )
    (net (code "98") (name "PL2{slash}IO47") (class "Default")
      (node (ref "IC1") (pin "37") (pinfunction "PL2(T5)_37") (pintype "bidirectional"))
      (node (ref "U2") (pin "47") (pinfunction "47_47") (pintype "bidirectional"))
    )
    (net (code "99") (name "PL3{slash}IO46~{}") (class "Default")
      (node (ref "IC1") (pin "38") (pinfunction "PL3(OC5A)_38") (pintype "bidirectional"))
      (node (ref "U2") (pin "46") (pinfunction "46_46") (pintype "bidirectional"))
    )
    (net (code "100") (name "PL4{slash}IO45~{}") (class "Default")
      (node (ref "IC1") (pin "39") (pinfunction "PL4(OC5B)_39") (pintype "bidirectional"))
      (node (ref "U2") (pin "45") (pinfunction "45_45") (pintype "bidirectional"))
    )
    (net (code "101") (name "PL5{slash}IO44~{}") (class "Default")
      (node (ref "IC1") (pin "40") (pinfunction "PL5(OC5C)_40") (pintype "bidirectional"))
      (node (ref "U2") (pin "44") (pinfunction "44_44") (pintype "bidirectional"))
    )
    (net (code "102") (name "PL6{slash}IO43") (class "Default")
      (node (ref "IC1") (pin "41") (pinfunction "PL6_41") (pintype "bidirectional"))
      (node (ref "U2") (pin "43") (pinfunction "43_43") (pintype "bidirectional"))
    )
    (net (code "103") (name "PL7{slash}IO42") (class "Default")
      (node (ref "IC1") (pin "42") (pinfunction "PL7_42") (pintype "bidirectional"))
      (node (ref "U2") (pin "42") (pinfunction "42_42") (pintype "bidirectional"))
    )
    (net (code "104") (name "RESET") (class "Default")
      (node (ref "C1") (pin "1") (pinfunction "1_1") (pintype "passive"))
      (node (ref "IC1") (pin "30") (pinfunction "RESET_30") (pintype "input"))
      (node (ref "IC3") (pin "13") (pinfunction "DTR_13") (pintype "bidirectional"))
      (node (ref "ICSP") (pin "5") (pinfunction "5_5") (pintype "passive"))
      (node (ref "R3") (pin "1") (pinfunction "1_1") (pintype "passive"))
      (node (ref "RESET") (pin "1") (pinfunction "1_1") (pintype "passive"))
      (node (ref "U2") (pin "RESET") (pinfunction "RESET_RESET") (pintype "bidirectional"))
    )
    (net (code "105") (name "RI") (class "Default")
      (node (ref "IC3") (pin "11") (pinfunction "RI_11") (pintype "bidirectional"))
      (node (ref "J5") (pin "4") (pinfunction "4_4") (pintype "passive"))
    )
    (net (code "106") (name "USB_N") (class "Default")
      (node (ref "IC3") (pin "6") (pinfunction "D-_6") (pintype "bidirectional"))
      (node (ref "J6") (pin "D-") (pinfunction "D-_D-") (pintype "bidirectional"))
    )
    (net (code "107") (name "USB_P") (class "Default")
      (node (ref "IC3") (pin "5") (pinfunction "D+_5") (pintype "bidirectional"))
      (node (ref "J6") (pin "D+") (pinfunction "D+_D+") (pintype "bidirectional"))
    )
    (net (code "108") (name "VIN") (class "Default")
      (node (ref "C10") (pin "1") (pinfunction "1_1") (pintype "passive"))
      (node (ref "D1") (pin "C") (pinfunction "C_C") (pintype "passive"))
      (node (ref "IC4") (pin "3") (pinfunction "IN_3") (pintype "input"))
      (node (ref "J4") (pin "PWR") (pinfunction "PWR_PWR") (pintype "bidirectional"))
      (node (ref "U2") (pin "VIN") (pinfunction "VIN_VIN") (pintype "bidirectional"))
    )
    (net (code "109") (name "XTAL1") (class "Default")
      (node (ref "IC1") (pin "34") (pinfunction "XTAL1_34") (pintype "input"))
      (node (ref "R1") (pin "1") (pinfunction "1_1") (pintype "passive"))
      (node (ref "Y1") (pin "3") (pinfunction "3_3") (pintype "passive"))
    )
    (net (code "110") (name "XTAL2") (class "Default")
      (node (ref "IC1") (pin "33") (pinfunction "XTAL2_33") (pintype "output"))
      (node (ref "R1") (pin "2") (pinfunction "2_2") (pintype "passive"))
      (node (ref "Y1") (pin "1") (pinfunction "1_1") (pintype "passive"))
    )
    (net (code "111") (name "unconnected-(IC3-RS232-Pad15)") (class "Default")
      (node (ref "IC3") (pin "15") (pinfunction "RS232_15") (pintype "bidirectional"))
    )
    (net (code "112") (name "unconnected-(IC3-RTS-Pad14)") (class "Default")
      (node (ref "IC3") (pin "14") (pinfunction "RTS_14") (pintype "bidirectional"))
    )
  )
)
